# monjolo.net
KiCad netlist of a schematic drawn in EAGLE
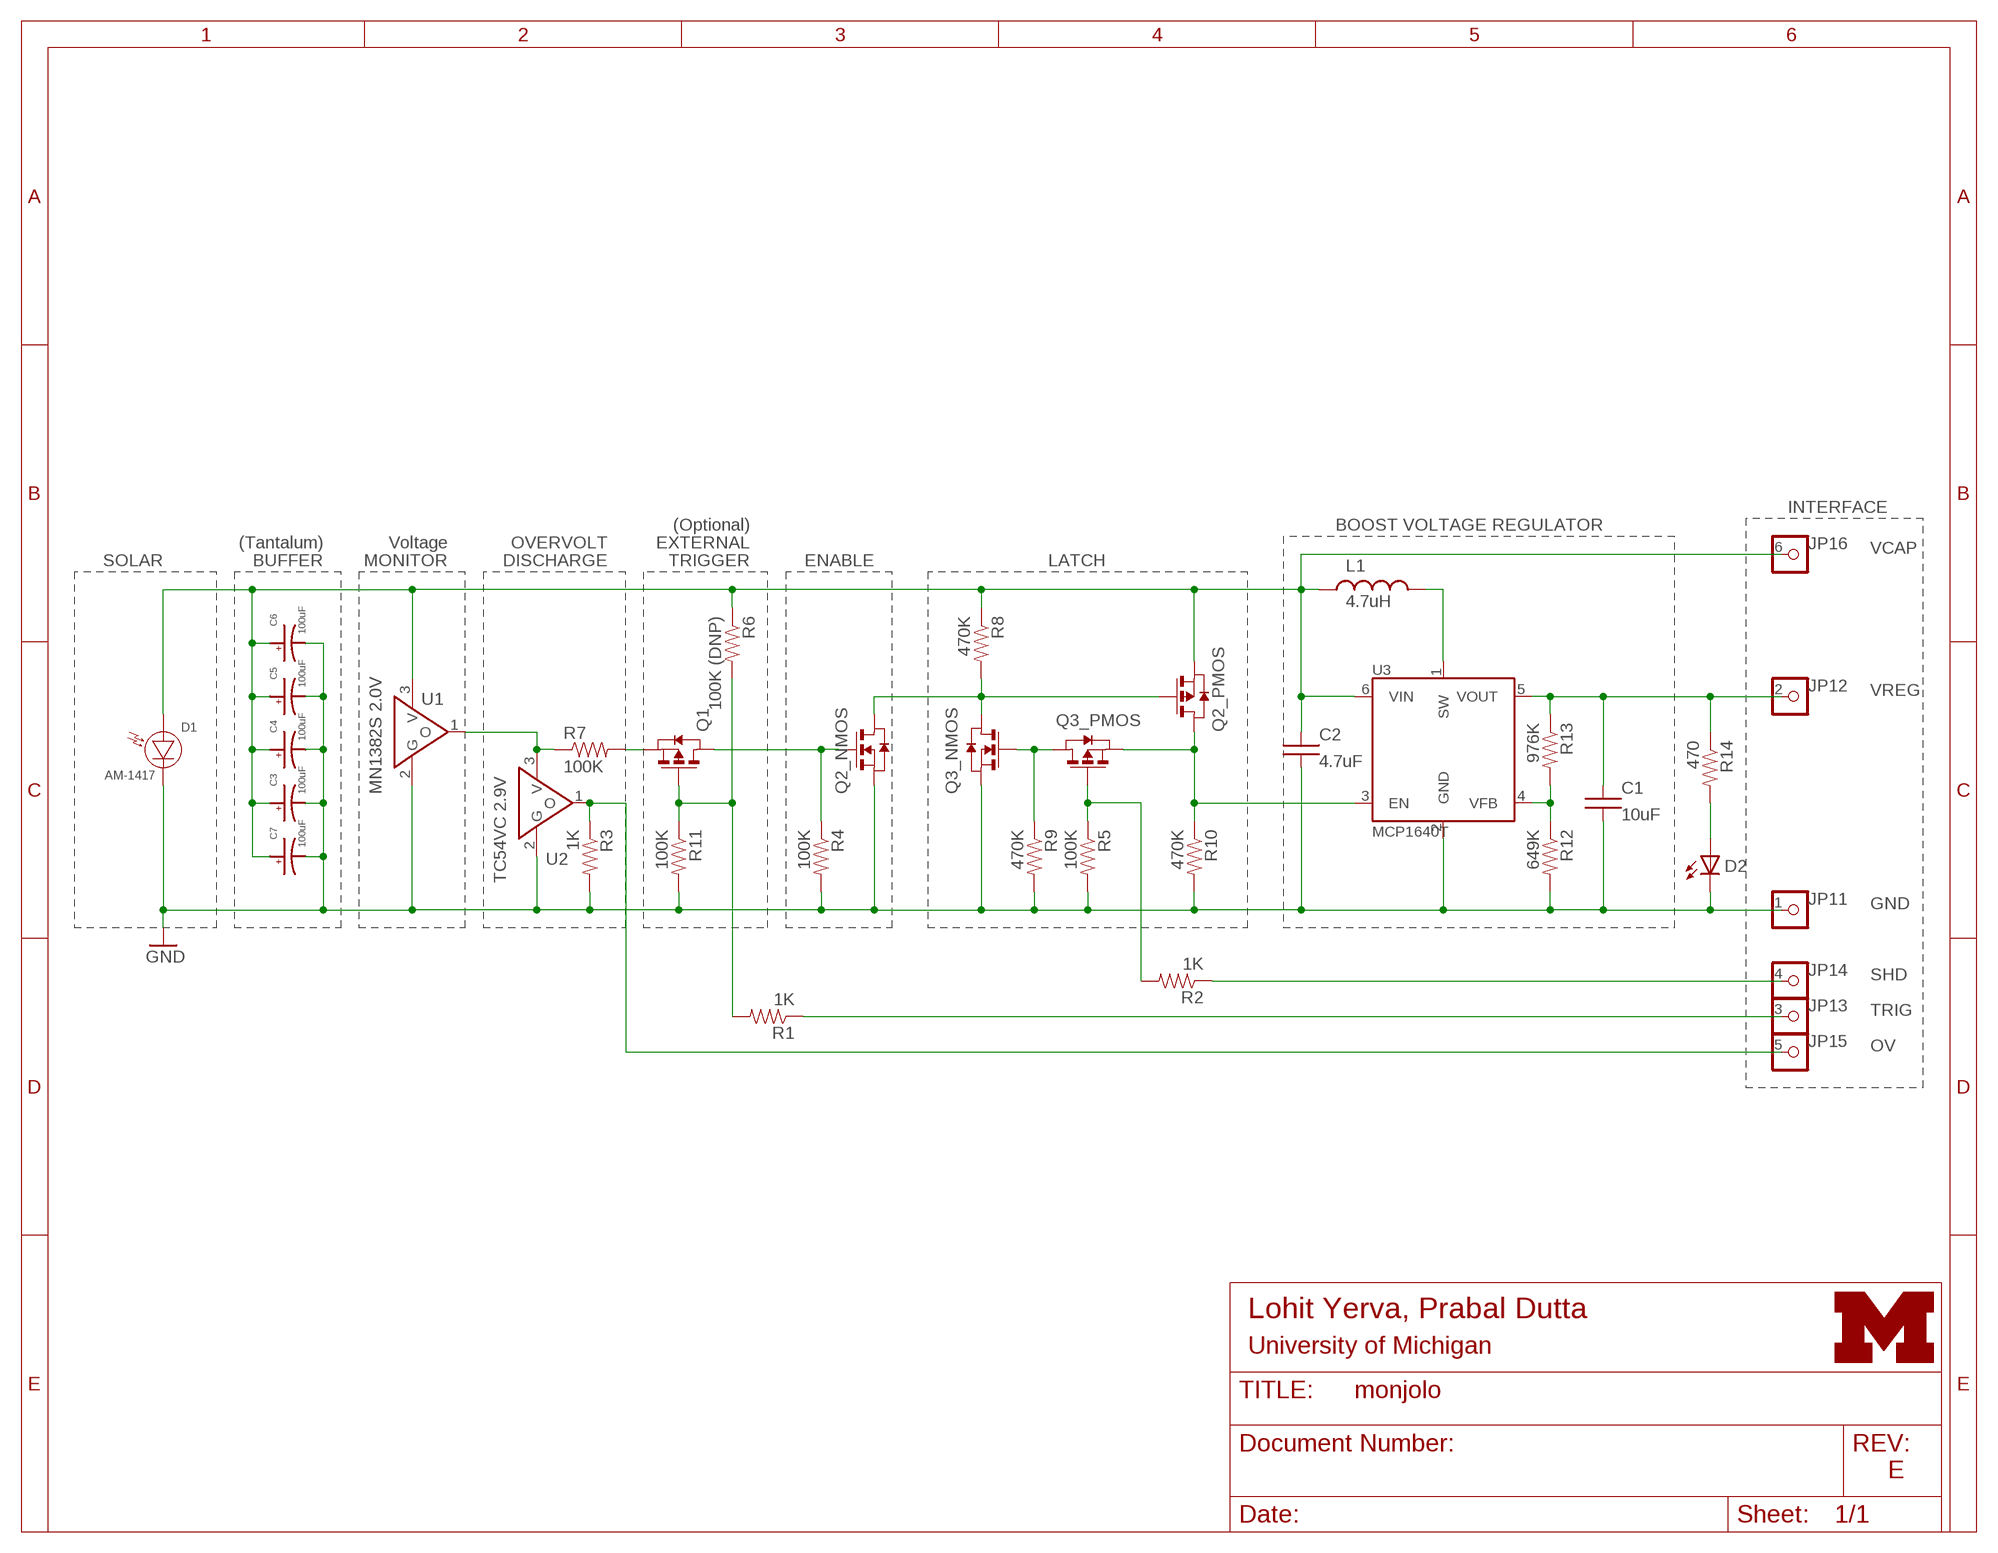
[diagram p0: schematic, sheet 1]

(export (version "E")
  (design (tool "Eeschema 10.0.6"))
  (components
    (comp (ref "C1")
      (value "10uF")
      (footprint "eagle-import:R0603B")
      (libsource (lib "eagle-import") (part "CAP"))
    )
    (comp (ref "C2")
      (value "4.7uF")
      (footprint "eagle-import:R0603B")
      (libsource (lib "eagle-import") (part "CAP"))
    )
    (comp (ref "C3")
      (value "100uF")
      (footprint "eagle-import:CAP1210")
      (libsource (lib "eagle-import") (part "1210_CAP_POLARIZED"))
    )
    (comp (ref "C4")
      (value "100uF")
      (footprint "eagle-import:CAP1210")
      (libsource (lib "eagle-import") (part "1210_CAP_POLARIZED"))
    )
    (comp (ref "C5")
      (value "100uF")
      (footprint "eagle-import:CAP1210")
      (libsource (lib "eagle-import") (part "1210_CAP_POLARIZED"))
    )
    (comp (ref "C6")
      (value "100uF")
      (footprint "eagle-import:CAP1210")
      (libsource (lib "eagle-import") (part "1210_CAP_POLARIZED"))
    )
    (comp (ref "C7")
      (value "100uF")
      (footprint "eagle-import:CAP1210")
      (libsource (lib "eagle-import") (part "1210_CAP_POLARIZED"))
    )
    (comp (ref "D1")
      (value "AM-1417")
      (footprint "eagle-import:SANYO-AM-1417")
      (libsource (lib "eagle-import") (part "AM-1417"))
    )
    (comp (ref "D2")
      (value "LED0603")
      (footprint "eagle-import:LED-0603")
      (libsource (lib "eagle-import") (part "LED0603"))
    )
    (comp (ref "JP1")
      (value "PINHD6")
      (footprint "eagle-import:HD6")
      (libsource (lib "eagle-import") (part "PINHD6"))
    )
    (comp (ref "L1")
      (value "4.7uH")
      (footprint "eagle-import:L2828")
      (libsource (lib "eagle-import") (part "L-US"))
    )
    (comp (ref "Q1")
      (value "PMOSSOT23")
      (footprint "eagle-import:SOT-23")
      (libsource (lib "eagle-import") (part "PMOSSOT23"))
    )
    (comp (ref "Q2")
      (value "DUAL_MOSFET_NP")
      (footprint "eagle-import:TSOP-6")
      (libsource (lib "eagle-import") (part "DUAL_MOSFET_NP"))
    )
    (comp (ref "Q3")
      (value "DUAL_MOSFET_NP")
      (footprint "eagle-import:TSOP-6")
      (libsource (lib "eagle-import") (part "DUAL_MOSFET_NP"))
    )
    (comp (ref "R1")
      (value "1K")
      (footprint "eagle-import:R0603B")
      (libsource (lib "eagle-import") (part "RESISTOR"))
    )
    (comp (ref "R2")
      (value "1K")
      (footprint "eagle-import:R0603B")
      (libsource (lib "eagle-import") (part "RESISTOR"))
    )
    (comp (ref "R3")
      (value "1K")
      (footprint "eagle-import:R0603B")
      (libsource (lib "eagle-import") (part "RESISTOR"))
    )
    (comp (ref "R4")
      (value "100K")
      (footprint "eagle-import:R0603B")
      (libsource (lib "eagle-import") (part "RESISTOR"))
    )
    (comp (ref "R5")
      (value "100K")
      (footprint "eagle-import:R0603B")
      (libsource (lib "eagle-import") (part "RESISTOR"))
    )
    (comp (ref "R6")
      (value "100K (DNP)")
      (footprint "eagle-import:R0603B")
      (libsource (lib "eagle-import") (part "RESISTOR"))
    )
    (comp (ref "R7")
      (value "100K")
      (footprint "eagle-import:R0603B")
      (libsource (lib "eagle-import") (part "RESISTOR"))
    )
    (comp (ref "R8")
      (value "470K")
      (footprint "eagle-import:R0603B")
      (libsource (lib "eagle-import") (part "RESISTOR"))
    )
    (comp (ref "R9")
      (value "470K")
      (footprint "eagle-import:R0603B")
      (libsource (lib "eagle-import") (part "RESISTOR"))
    )
    (comp (ref "R10")
      (value "470K")
      (footprint "eagle-import:R0603B")
      (libsource (lib "eagle-import") (part "RESISTOR"))
    )
    (comp (ref "R11")
      (value "100K")
      (footprint "eagle-import:R0603B")
      (libsource (lib "eagle-import") (part "RESISTOR"))
    )
    (comp (ref "R12")
      (value "649K")
      (footprint "eagle-import:R0603B")
      (libsource (lib "eagle-import") (part "RESISTOR"))
    )
    (comp (ref "R13")
      (value "976K")
      (footprint "eagle-import:R0603B")
      (libsource (lib "eagle-import") (part "RESISTOR"))
    )
    (comp (ref "R14")
      (value "470")
      (footprint "eagle-import:R0603B")
      (libsource (lib "eagle-import") (part "RESISTOR"))
    )
    (comp (ref "U$1")
      (value "UMICH_SOLID_SMALL")
      (footprint "eagle-import:UMICH_SOLID_75MIL")
      (libsource (lib "eagle-import") (part "UMICH_SOLID_SMALL"))
    )
    (comp (ref "U1")
      (value "MN1382S 2.0V")
      (footprint "eagle-import:MINI-3DC")
      (libsource (lib "eagle-import") (part "MN1382S"))
    )
    (comp (ref "U2")
      (value "TC54VC 2.9V")
      (footprint "eagle-import:MINI-3DC")
      (libsource (lib "eagle-import") (part "MN1382S"))
    )
    (comp (ref "U3")
      (value "MCP1640T")
      (footprint "eagle-import:SOT-23-6")
      (libsource (lib "eagle-import") (part "MCP1640"))
    )
  )
  (nets
    (net (code "1") (name "GND") (class "Default")
      (node (ref "C1") (pin "2") (pinfunction "2_2") (pintype "bidirectional"))
      (node (ref "C2") (pin "2") (pinfunction "2_2") (pintype "bidirectional"))
      (node (ref "C3") (pin "ANODE") (pinfunction "ANODE_ANODE") (pintype "bidirectional"))
      (node (ref "C4") (pin "ANODE") (pinfunction "ANODE_ANODE") (pintype "bidirectional"))
      (node (ref "C5") (pin "ANODE") (pinfunction "ANODE_ANODE") (pintype "bidirectional"))
      (node (ref "C6") (pin "ANODE") (pinfunction "ANODE_ANODE") (pintype "bidirectional"))
      (node (ref "C7") (pin "ANODE") (pinfunction "ANODE_ANODE") (pintype "bidirectional"))
      (node (ref "D1") (pin "NEG") (pinfunction "C_NEG") (pintype "bidirectional"))
      (node (ref "D2") (pin "C") (pinfunction "C_C") (pintype "passive"))
      (node (ref "JP1") (pin "1") (pinfunction "1_1") (pintype "passive"))
      (node (ref "Q2") (pin "5") (pinfunction "S_5") (pintype "passive"))
      (node (ref "Q3") (pin "5") (pinfunction "S_5") (pintype "passive"))
      (node (ref "R10") (pin "2") (pinfunction "2_2") (pintype "passive"))
      (node (ref "R11") (pin "2") (pinfunction "2_2") (pintype "passive"))
      (node (ref "R12") (pin "2") (pinfunction "2_2") (pintype "passive"))
      (node (ref "R3") (pin "2") (pinfunction "2_2") (pintype "passive"))
      (node (ref "R4") (pin "2") (pinfunction "2_2") (pintype "passive"))
      (node (ref "R5") (pin "2") (pinfunction "2_2") (pintype "passive"))
      (node (ref "R9") (pin "2") (pinfunction "2_2") (pintype "passive"))
      (node (ref "U1") (pin "2") (pinfunction "G_2") (pintype "power_in"))
      (node (ref "U2") (pin "2") (pinfunction "G_2") (pintype "power_in"))
      (node (ref "U3") (pin "2") (pinfunction "GND_2") (pintype "power_in"))
    )
    (net (code "2") (name "Net-(D1-A)") (class "Default")
      (node (ref "C2") (pin "1") (pinfunction "1_1") (pintype "bidirectional"))
      (node (ref "C3") (pin "CATHODE") (pinfunction "CATHODE_CATHODE") (pintype "bidirectional"))
      (node (ref "C4") (pin "CATHODE") (pinfunction "CATHODE_CATHODE") (pintype "bidirectional"))
      (node (ref "C5") (pin "CATHODE") (pinfunction "CATHODE_CATHODE") (pintype "bidirectional"))
      (node (ref "C6") (pin "CATHODE") (pinfunction "CATHODE_CATHODE") (pintype "bidirectional"))
      (node (ref "C7") (pin "CATHODE") (pinfunction "CATHODE_CATHODE") (pintype "bidirectional"))
      (node (ref "D1") (pin "POS") (pinfunction "A_POS") (pintype "bidirectional"))
      (node (ref "JP1") (pin "6") (pinfunction "1_6") (pintype "passive"))
      (node (ref "L1") (pin "1") (pinfunction "1_1") (pintype "passive"))
      (node (ref "Q2") (pin "2") (pinfunction "S_2") (pintype "passive"))
      (node (ref "R6") (pin "1") (pinfunction "1_1") (pintype "passive"))
      (node (ref "R8") (pin "1") (pinfunction "1_1") (pintype "passive"))
      (node (ref "U1") (pin "3") (pinfunction "V_3") (pintype "power_in"))
      (node (ref "U3") (pin "6") (pinfunction "VIN_6") (pintype "input"))
    )
    (net (code "3") (name "Net-(D2-PadA)") (class "Default")
      (node (ref "D2") (pin "A") (pinfunction "A_A") (pintype "passive"))
      (node (ref "R14") (pin "2") (pinfunction "2_2") (pintype "passive"))
    )
    (net (code "4") (name "Net-(JP1B-1)") (class "Default")
      (node (ref "C1") (pin "1") (pinfunction "1_1") (pintype "bidirectional"))
      (node (ref "JP1") (pin "2") (pinfunction "1_2") (pintype "passive"))
      (node (ref "R13") (pin "1") (pinfunction "1_1") (pintype "passive"))
      (node (ref "R14") (pin "1") (pinfunction "1_1") (pintype "passive"))
      (node (ref "U3") (pin "5") (pinfunction "VOUT_5") (pintype "output"))
    )
    (net (code "5") (name "Net-(JP1C-1)") (class "Default")
      (node (ref "JP1") (pin "3") (pinfunction "1_3") (pintype "passive"))
      (node (ref "R1") (pin "1") (pinfunction "1_1") (pintype "passive"))
    )
    (net (code "6") (name "Net-(JP1D-1)") (class "Default")
      (node (ref "JP1") (pin "4") (pinfunction "1_4") (pintype "passive"))
      (node (ref "R2") (pin "1") (pinfunction "1_1") (pintype "passive"))
    )
    (net (code "7") (name "Net-(JP1E-1)") (class "Default")
      (node (ref "JP1") (pin "5") (pinfunction "1_5") (pintype "passive"))
      (node (ref "R3") (pin "1") (pinfunction "1_1") (pintype "passive"))
      (node (ref "U2") (pin "1") (pinfunction "O_1") (pintype "output"))
    )
    (net (code "8") (name "Net-(Q1-D)") (class "Default")
      (node (ref "Q1") (pin "1") (pinfunction "D_1") (pintype "passive"))
      (node (ref "Q2") (pin "1") (pinfunction "G_1") (pintype "passive"))
      (node (ref "R4") (pin "1") (pinfunction "1_1") (pintype "passive"))
    )
    (net (code "9") (name "Net-(Q1-G)") (class "Default")
      (node (ref "Q1") (pin "3") (pinfunction "G_3") (pintype "passive"))
      (node (ref "R1") (pin "2") (pinfunction "2_2") (pintype "passive"))
      (node (ref "R11") (pin "1") (pinfunction "1_1") (pintype "passive"))
      (node (ref "R6") (pin "2") (pinfunction "2_2") (pintype "passive"))
    )
    (net (code "10") (name "Net-(Q1-S)") (class "Default")
      (node (ref "Q1") (pin "2") (pinfunction "S_2") (pintype "passive"))
      (node (ref "R7") (pin "2") (pinfunction "2_2") (pintype "passive"))
    )
    (net (code "11") (name "Net-(Q2A-D)") (class "Default")
      (node (ref "Q2") (pin "3") (pinfunction "G_3") (pintype "passive"))
      (node (ref "Q2") (pin "6") (pinfunction "D_6") (pintype "passive"))
      (node (ref "Q3") (pin "6") (pinfunction "D_6") (pintype "passive"))
      (node (ref "R8") (pin "2") (pinfunction "2_2") (pintype "passive"))
    )
    (net (code "12") (name "Net-(Q2B-D)") (class "Default")
      (node (ref "Q2") (pin "4") (pinfunction "D_4") (pintype "passive"))
      (node (ref "Q3") (pin "2") (pinfunction "S_2") (pintype "passive"))
      (node (ref "R10") (pin "1") (pinfunction "1_1") (pintype "passive"))
      (node (ref "U3") (pin "3") (pinfunction "EN_3") (pintype "input"))
    )
    (net (code "13") (name "Net-(Q3A-G)") (class "Default")
      (node (ref "Q3") (pin "1") (pinfunction "G_1") (pintype "passive"))
      (node (ref "Q3") (pin "4") (pinfunction "D_4") (pintype "passive"))
      (node (ref "R9") (pin "1") (pinfunction "1_1") (pintype "passive"))
    )
    (net (code "14") (name "Net-(Q3B-G)") (class "Default")
      (node (ref "Q3") (pin "3") (pinfunction "G_3") (pintype "passive"))
      (node (ref "R2") (pin "2") (pinfunction "2_2") (pintype "passive"))
      (node (ref "R5") (pin "1") (pinfunction "1_1") (pintype "passive"))
    )
    (net (code "15") (name "Net-(U1-O)") (class "Default")
      (node (ref "R7") (pin "1") (pinfunction "1_1") (pintype "passive"))
      (node (ref "U1") (pin "1") (pinfunction "O_1") (pintype "output"))
      (node (ref "U2") (pin "3") (pinfunction "V_3") (pintype "power_in"))
    )
    (net (code "16") (name "Net-(U3-SW)") (class "Default")
      (node (ref "L1") (pin "2") (pinfunction "2_2") (pintype "passive"))
      (node (ref "U3") (pin "1") (pinfunction "SW_1") (pintype "bidirectional"))
    )
    (net (code "17") (name "Net-(U3-VFB)") (class "Default")
      (node (ref "R12") (pin "1") (pinfunction "1_1") (pintype "passive"))
      (node (ref "R13") (pin "2") (pinfunction "2_2") (pintype "passive"))
      (node (ref "U3") (pin "4") (pinfunction "VFB_4") (pintype "input"))
    )
  )
)
